# esp32_shield.net
KiCad netlist of a schematic drawn in EAGLE
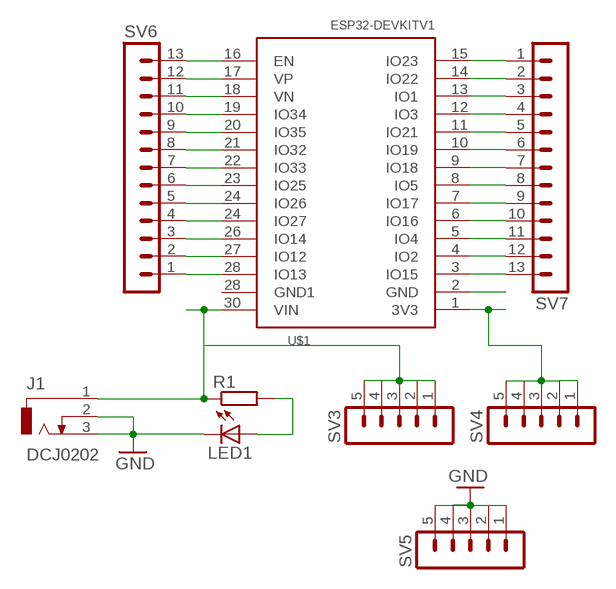
[diagram p0: schematic, sheet 1]

(export (version "E")
  (design (tool "Eeschema 10.0.6"))
  (components
    (comp (ref "J1")
      (value "DCJ0202")
      (footprint "eagle-import:DCJ0202")
      (libsource (lib "eagle-import") (part "DCJ0202"))
    )
    (comp (ref "LED1")
      (value "LED5MM")
      (footprint "eagle-import:LED5MM")
      (libsource (lib "eagle-import") (part "LED5MM"))
    )
    (comp (ref "R1")
      (value "R-EU_0204/7")
      (footprint "eagle-import:0204_7")
      (libsource (lib "eagle-import") (part "R-EU_0204/7"))
    )
    (comp (ref "SV3")
      (value "MA05-1")
      (footprint "eagle-import:MA05-1")
      (libsource (lib "eagle-import") (part "MA05-1"))
    )
    (comp (ref "SV4")
      (value "MA05-1")
      (footprint "eagle-import:MA05-1")
      (libsource (lib "eagle-import") (part "MA05-1"))
    )
    (comp (ref "SV5")
      (value "MA05-1")
      (footprint "eagle-import:MA05-1")
      (libsource (lib "eagle-import") (part "MA05-1"))
    )
    (comp (ref "SV6")
      (value "MA13-1")
      (footprint "eagle-import:MA13-1")
      (libsource (lib "eagle-import") (part "MA13-1"))
    )
    (comp (ref "SV7")
      (value "MA13-1")
      (footprint "eagle-import:MA13-1")
      (libsource (lib "eagle-import") (part "MA13-1"))
    )
    (comp (ref "U$1")
      (value "ESP32DEVKITV1")
      (footprint "eagle-import:ESP32-DEVKITV1")
      (libsource (lib "eagle-import") (part "ESP32DEVKITV1"))
    )
  )
  (nets
    (net (code "1") (name "GND") (class "Default")
      (node (ref "J1") (pin "2") (pinfunction "2_2") (pintype "passive"))
      (node (ref "J1") (pin "3") (pinfunction "3_3") (pintype "passive"))
      (node (ref "LED1") (pin "K") (pinfunction "C_K") (pintype "passive"))
      (node (ref "SV5") (pin "1") (pinfunction "1_1") (pintype "passive"))
      (node (ref "SV5") (pin "2") (pinfunction "2_2") (pintype "passive"))
      (node (ref "SV5") (pin "3") (pinfunction "3_3") (pintype "passive"))
      (node (ref "SV5") (pin "4") (pinfunction "4_4") (pintype "passive"))
      (node (ref "SV5") (pin "5") (pinfunction "5_5") (pintype "passive"))
    )
    (net (code "2") (name "Net-(LED1-PadA)") (class "Default")
      (node (ref "LED1") (pin "A") (pinfunction "A_A") (pintype "passive"))
      (node (ref "R1") (pin "2") (pinfunction "2_2") (pintype "passive"))
    )
    (net (code "3") (name "Net-(U$1-3V3)") (class "Default")
      (node (ref "SV4") (pin "1") (pinfunction "1_1") (pintype "passive"))
      (node (ref "SV4") (pin "2") (pinfunction "2_2") (pintype "passive"))
      (node (ref "SV4") (pin "3") (pinfunction "3_3") (pintype "passive"))
      (node (ref "SV4") (pin "4") (pinfunction "4_4") (pintype "passive"))
      (node (ref "SV4") (pin "5") (pinfunction "5_5") (pintype "passive"))
      (node (ref "U$1") (pin "1") (pinfunction "3V3_1") (pintype "bidirectional"))
    )
    (net (code "4") (name "Net-(U$1-EN)") (class "Default")
      (node (ref "SV6") (pin "13") (pinfunction "13_13") (pintype "passive"))
      (node (ref "U$1") (pin "16") (pinfunction "EN_16") (pintype "bidirectional"))
    )
    (net (code "5") (name "Net-(U$1-IO1)") (class "Default")
      (node (ref "SV7") (pin "3") (pinfunction "3_3") (pintype "passive"))
      (node (ref "U$1") (pin "13") (pinfunction "IO1_13") (pintype "bidirectional"))
    )
    (net (code "6") (name "Net-(U$1-IO2)") (class "Default")
      (node (ref "SV7") (pin "12") (pinfunction "12_12") (pintype "passive"))
      (node (ref "U$1") (pin "4") (pinfunction "IO2_4") (pintype "bidirectional"))
    )
    (net (code "7") (name "Net-(U$1-IO3)") (class "Default")
      (node (ref "SV7") (pin "4") (pinfunction "4_4") (pintype "passive"))
      (node (ref "U$1") (pin "12") (pinfunction "IO3_12") (pintype "bidirectional"))
    )
    (net (code "8") (name "Net-(U$1-IO4)") (class "Default")
      (node (ref "SV7") (pin "11") (pinfunction "11_11") (pintype "passive"))
      (node (ref "U$1") (pin "5") (pinfunction "IO4_5") (pintype "bidirectional"))
    )
    (net (code "9") (name "Net-(U$1-IO5)") (class "Default")
      (node (ref "SV7") (pin "8") (pinfunction "8_8") (pintype "passive"))
      (node (ref "U$1") (pin "8") (pinfunction "IO5_8") (pintype "bidirectional"))
    )
    (net (code "10") (name "Net-(U$1-IO12)") (class "Default")
      (node (ref "SV6") (pin "2") (pinfunction "2_2") (pintype "passive"))
      (node (ref "U$1") (pin "27") (pinfunction "IO12_27") (pintype "bidirectional"))
    )
    (net (code "11") (name "Net-(U$1-IO13)") (class "Default")
      (node (ref "SV6") (pin "1") (pinfunction "1_1") (pintype "passive"))
      (node (ref "U$1") (pin "28") (pinfunction "IO13_28") (pintype "bidirectional"))
    )
    (net (code "12") (name "Net-(U$1-IO14)") (class "Default")
      (node (ref "SV6") (pin "3") (pinfunction "3_3") (pintype "passive"))
      (node (ref "U$1") (pin "26") (pinfunction "IO14_26") (pintype "bidirectional"))
    )
    (net (code "13") (name "Net-(U$1-IO15)") (class "Default")
      (node (ref "SV7") (pin "13") (pinfunction "13_13") (pintype "passive"))
      (node (ref "U$1") (pin "3") (pinfunction "IO15_3") (pintype "bidirectional"))
    )
    (net (code "14") (name "Net-(U$1-IO16)") (class "Default")
      (node (ref "SV7") (pin "10") (pinfunction "10_10") (pintype "passive"))
      (node (ref "U$1") (pin "6") (pinfunction "IO16_6") (pintype "bidirectional"))
    )
    (net (code "15") (name "Net-(U$1-IO17)") (class "Default")
      (node (ref "SV7") (pin "9") (pinfunction "9_9") (pintype "passive"))
      (node (ref "U$1") (pin "7") (pinfunction "IO17_7") (pintype "bidirectional"))
    )
    (net (code "16") (name "Net-(U$1-IO18)") (class "Default")
      (node (ref "SV7") (pin "7") (pinfunction "7_7") (pintype "passive"))
      (node (ref "U$1") (pin "9") (pinfunction "IO18_9") (pintype "bidirectional"))
    )
    (net (code "17") (name "Net-(U$1-IO19)") (class "Default")
      (node (ref "SV7") (pin "6") (pinfunction "6_6") (pintype "passive"))
      (node (ref "U$1") (pin "10") (pinfunction "IO19_10") (pintype "bidirectional"))
    )
    (net (code "18") (name "Net-(U$1-IO21)") (class "Default")
      (node (ref "SV7") (pin "5") (pinfunction "5_5") (pintype "passive"))
      (node (ref "U$1") (pin "11") (pinfunction "IO21_11") (pintype "bidirectional"))
    )
    (net (code "19") (name "Net-(U$1-IO22)") (class "Default")
      (node (ref "SV7") (pin "2") (pinfunction "2_2") (pintype "passive"))
      (node (ref "U$1") (pin "14") (pinfunction "IO22_14") (pintype "bidirectional"))
    )
    (net (code "20") (name "Net-(U$1-IO23)") (class "Default")
      (node (ref "SV7") (pin "1") (pinfunction "1_1") (pintype "passive"))
      (node (ref "U$1") (pin "15") (pinfunction "IO23_15") (pintype "bidirectional"))
    )
    (net (code "21") (name "Net-(U$1-IO25)") (class "Default")
      (node (ref "SV6") (pin "6") (pinfunction "6_6") (pintype "passive"))
      (node (ref "U$1") (pin "23") (pinfunction "IO25_23") (pintype "bidirectional"))
    )
    (net (code "22") (name "Net-(U$1-IO26)") (class "Default")
      (node (ref "SV6") (pin "5") (pinfunction "5_5") (pintype "passive"))
      (node (ref "U$1") (pin "24") (pinfunction "IO26_24") (pintype "bidirectional"))
    )
    (net (code "23") (name "Net-(U$1-IO27)") (class "Default")
      (node (ref "SV6") (pin "4") (pinfunction "4_4") (pintype "passive"))
      (node (ref "U$1") (pin "24") (pinfunction "IO27_24") (pintype "bidirectional"))
    )
    (net (code "24") (name "Net-(U$1-IO32)") (class "Default")
      (node (ref "SV6") (pin "8") (pinfunction "8_8") (pintype "passive"))
      (node (ref "U$1") (pin "21") (pinfunction "IO32_21") (pintype "bidirectional"))
    )
    (net (code "25") (name "Net-(U$1-IO33)") (class "Default")
      (node (ref "SV6") (pin "7") (pinfunction "7_7") (pintype "passive"))
      (node (ref "U$1") (pin "22") (pinfunction "IO33_22") (pintype "bidirectional"))
    )
    (net (code "26") (name "Net-(U$1-IO34)") (class "Default")
      (node (ref "SV6") (pin "10") (pinfunction "10_10") (pintype "passive"))
      (node (ref "U$1") (pin "19") (pinfunction "IO34_19") (pintype "bidirectional"))
    )
    (net (code "27") (name "Net-(U$1-IO35)") (class "Default")
      (node (ref "SV6") (pin "9") (pinfunction "9_9") (pintype "passive"))
      (node (ref "U$1") (pin "20") (pinfunction "IO35_20") (pintype "bidirectional"))
    )
    (net (code "28") (name "Net-(U$1-VIN)") (class "Default")
      (node (ref "J1") (pin "1") (pinfunction "1_1") (pintype "passive"))
      (node (ref "R1") (pin "1") (pinfunction "1_1") (pintype "passive"))
      (node (ref "SV3") (pin "1") (pinfunction "1_1") (pintype "passive"))
      (node (ref "SV3") (pin "2") (pinfunction "2_2") (pintype "passive"))
      (node (ref "SV3") (pin "3") (pinfunction "3_3") (pintype "passive"))
      (node (ref "SV3") (pin "4") (pinfunction "4_4") (pintype "passive"))
      (node (ref "SV3") (pin "5") (pinfunction "5_5") (pintype "passive"))
      (node (ref "U$1") (pin "30") (pinfunction "VIN_30") (pintype "bidirectional"))
    )
    (net (code "29") (name "Net-(U$1-VN)") (class "Default")
      (node (ref "SV6") (pin "11") (pinfunction "11_11") (pintype "passive"))
      (node (ref "U$1") (pin "18") (pinfunction "VN_18") (pintype "bidirectional"))
    )
    (net (code "30") (name "Net-(U$1-VP)") (class "Default")
      (node (ref "SV6") (pin "12") (pinfunction "12_12") (pintype "passive"))
      (node (ref "U$1") (pin "17") (pinfunction "VP_17") (pintype "bidirectional"))
    )
    (net (code "31") (name "unconnected-(U$1-GND-Pad2)") (class "Default")
      (node (ref "U$1") (pin "2") (pinfunction "GND_2") (pintype "bidirectional"))
    )
    (net (code "32") (name "unconnected-(U$1-GND1-Pad28)") (class "Default")
      (node (ref "U$1") (pin "28") (pinfunction "GND1_28") (pintype "bidirectional"))
    )
  )
)
